# ma_esquema.net
KiCad netlist of a schematic drawn in EAGLE
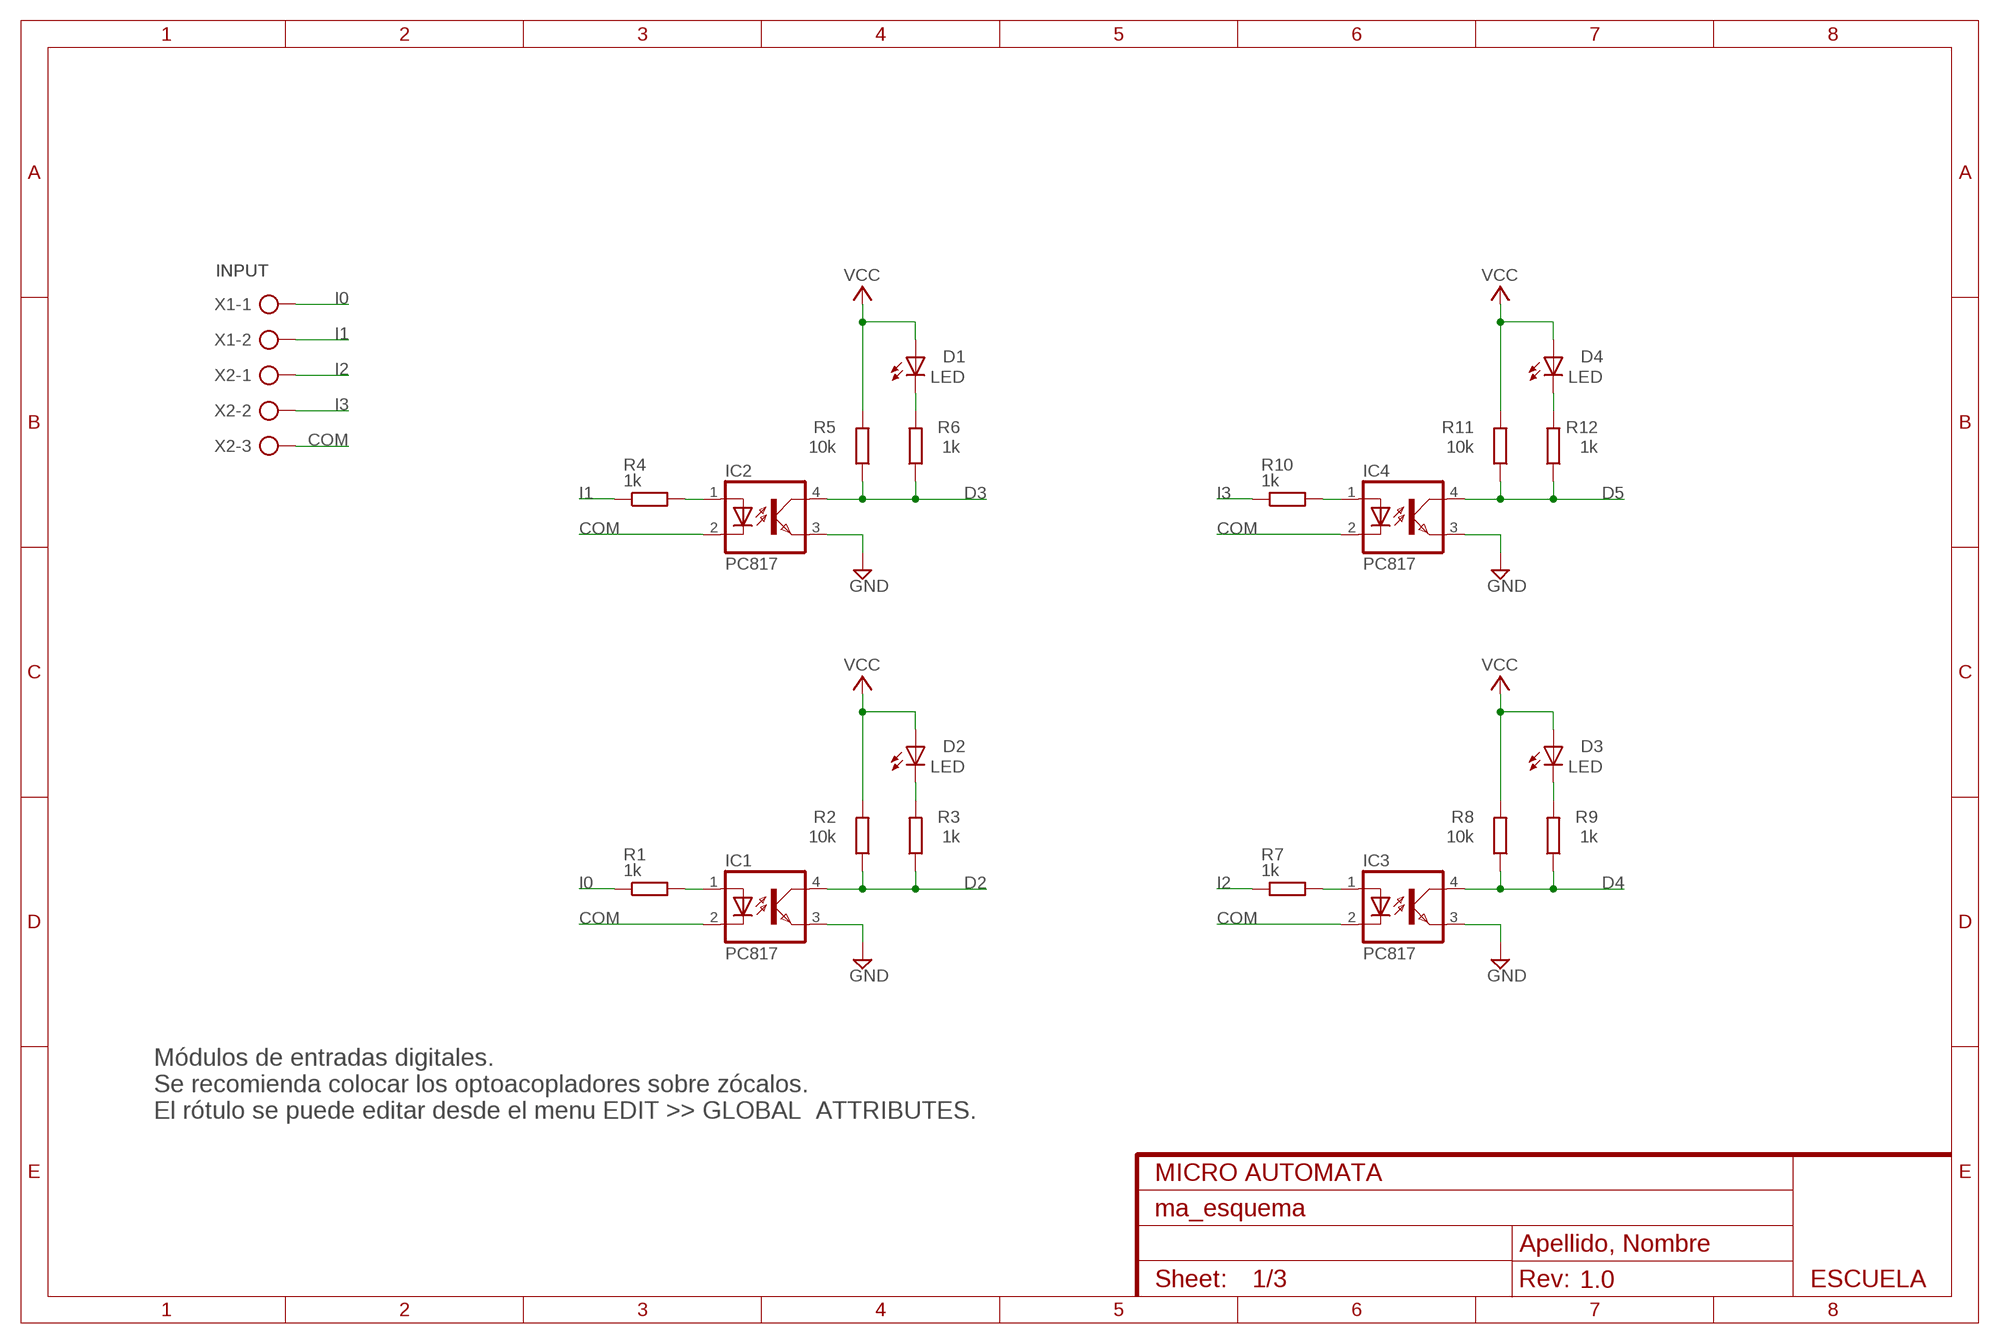
[diagram p0: schematic, sheet 1]
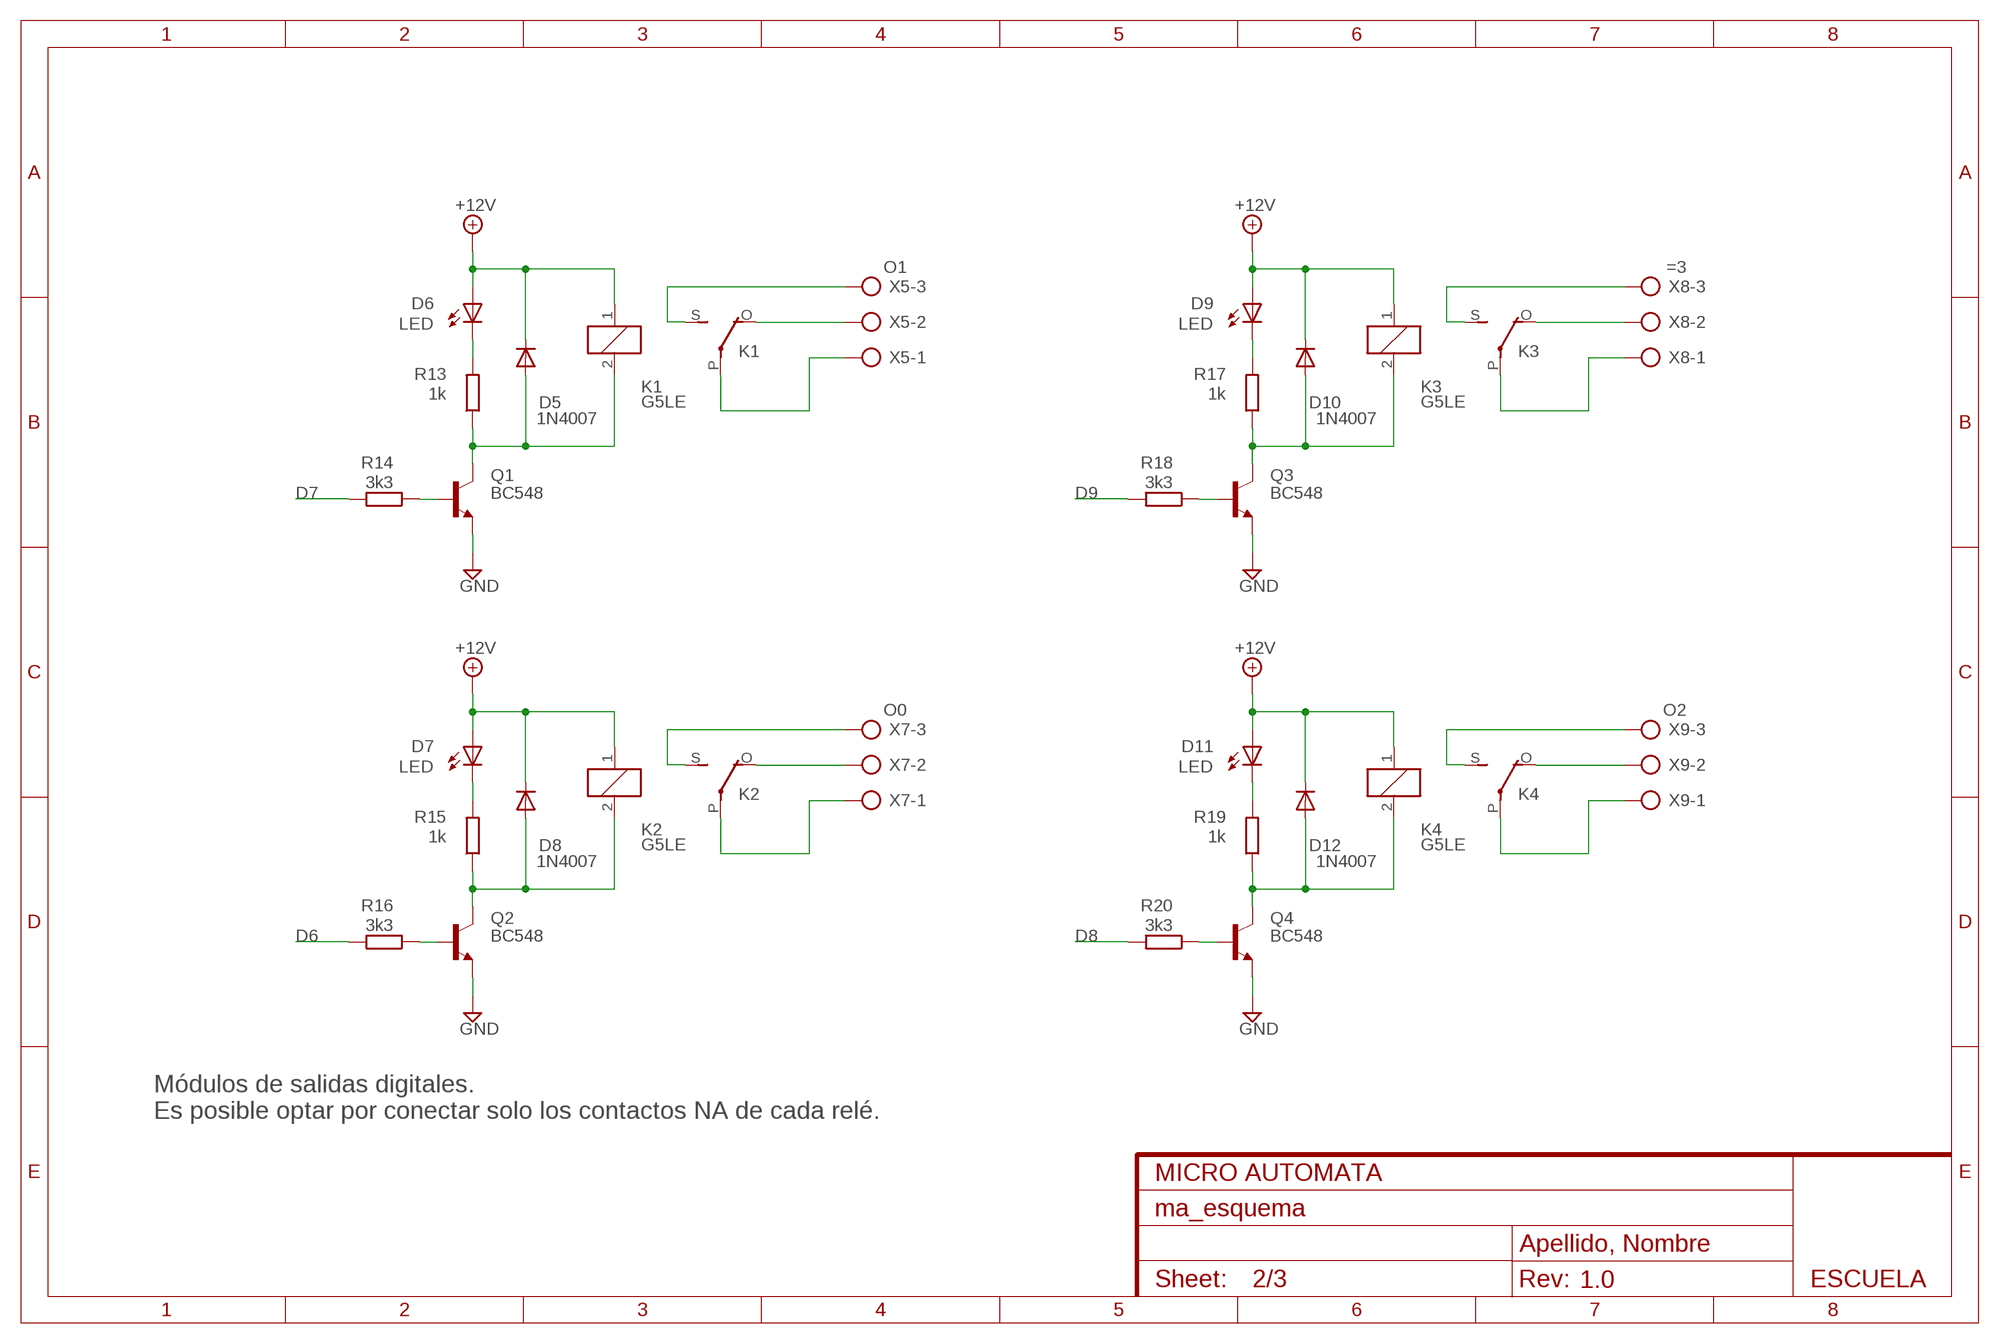
[diagram p1: schematic, sheet 2]
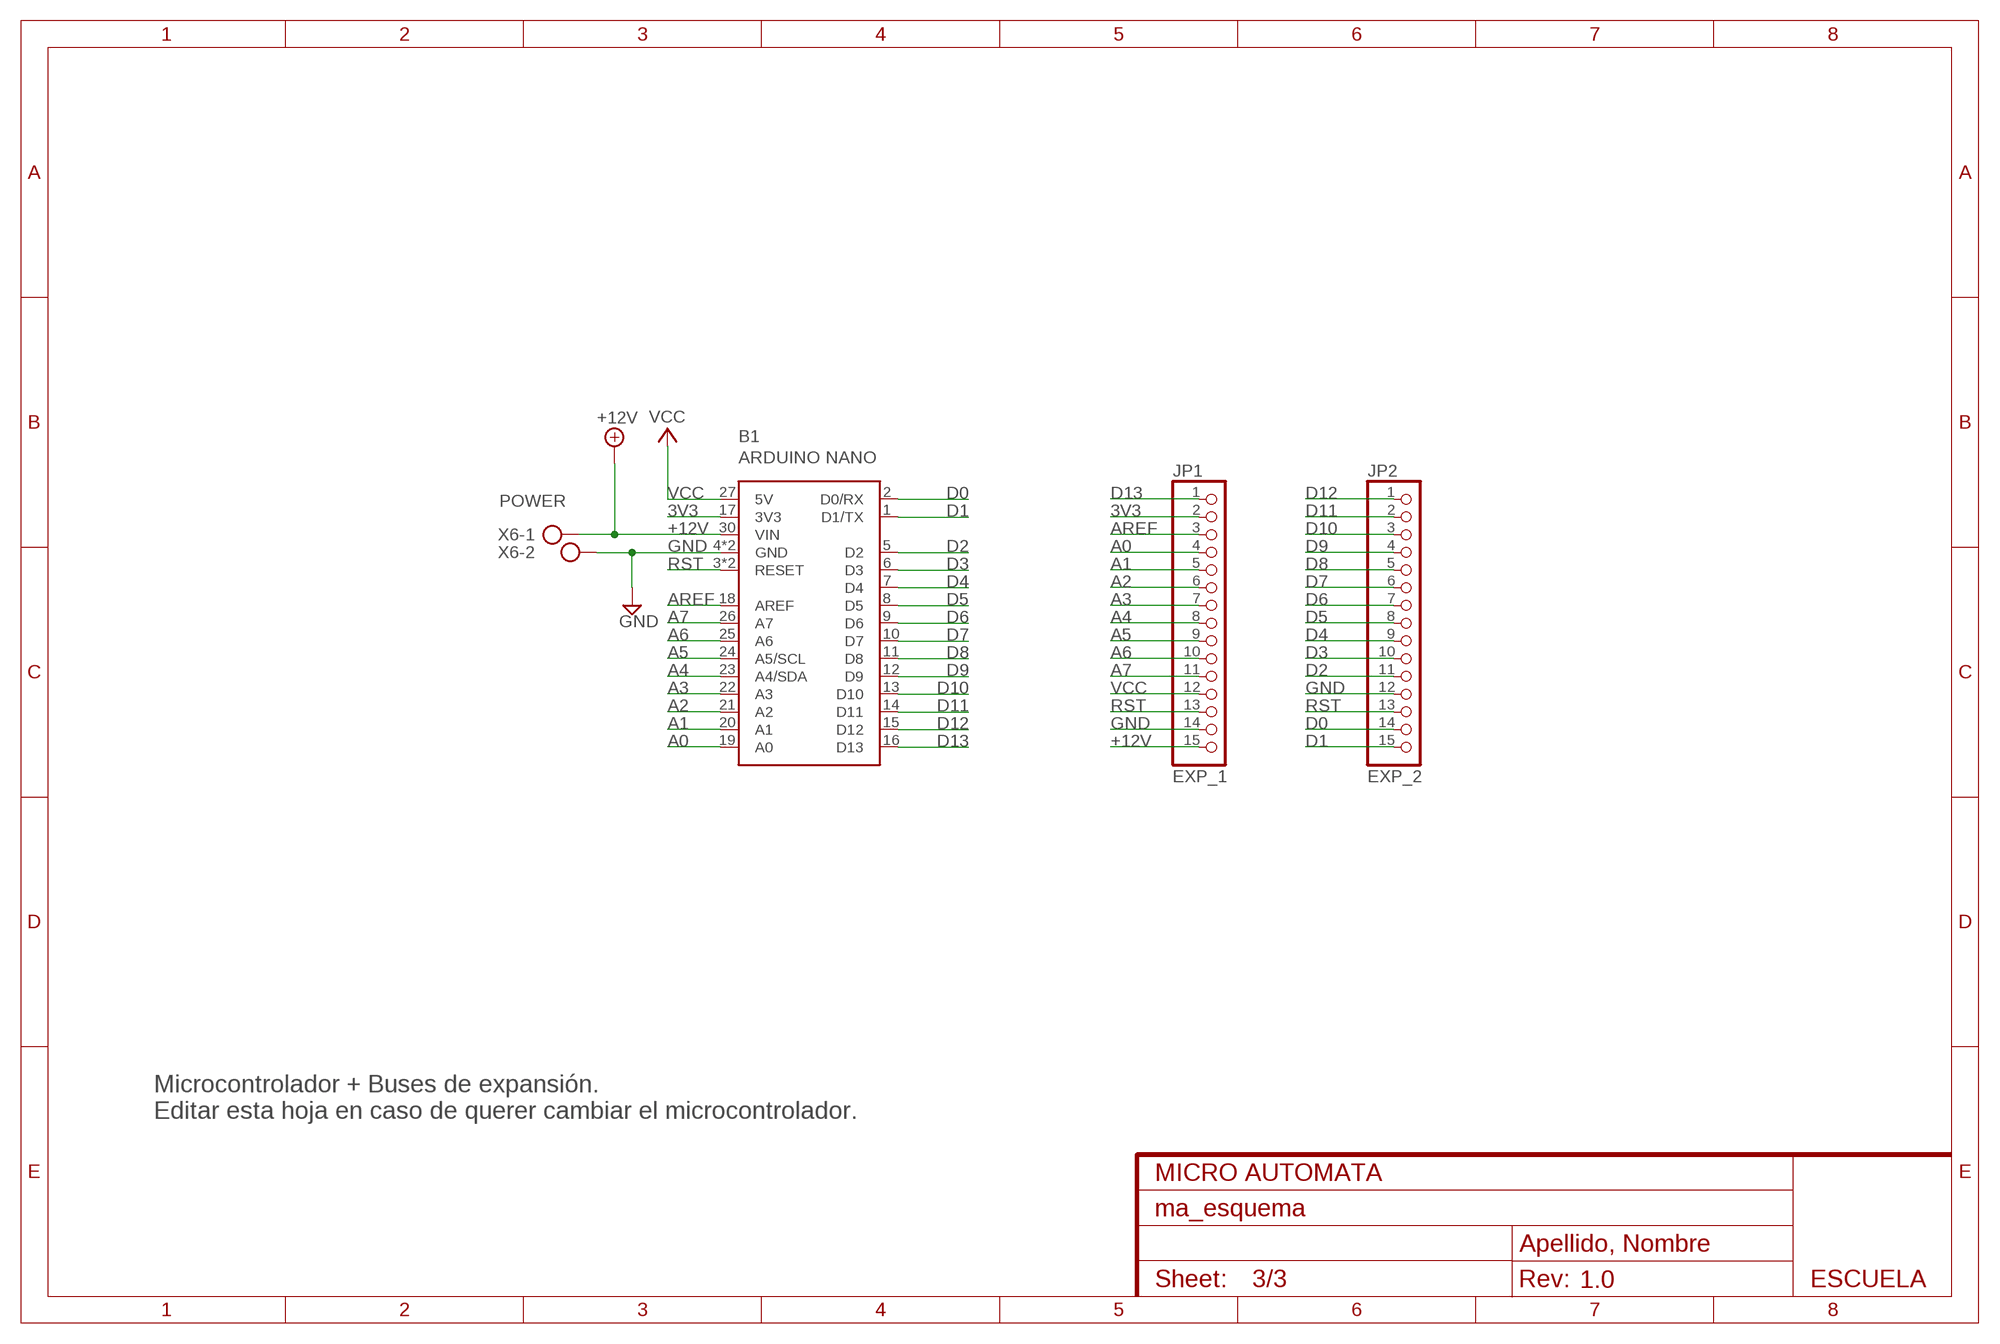
[diagram p2: schematic, sheet 3]

(export (version "E")
  (design (tool "Eeschema 10.0.6"))
  (components
    (comp (ref "D1")
      (value "LED")
      (footprint "eagle-import:LED_3MM")
      (libsource (lib "eagle-import") (part "LED3MM"))
    )
    (comp (ref "D2")
      (value "LED")
      (footprint "eagle-import:LED_3MM")
      (libsource (lib "eagle-import") (part "LED3MM"))
    )
    (comp (ref "D3")
      (value "LED")
      (footprint "eagle-import:LED_3MM")
      (libsource (lib "eagle-import") (part "LED3MM"))
    )
    (comp (ref "D4")
      (value "LED")
      (footprint "eagle-import:LED_3MM")
      (libsource (lib "eagle-import") (part "LED3MM"))
    )
    (comp (ref "IC1")
      (value "PC817")
      (footprint "eagle-import:DIL04")
      (fields (field (name "MPN") "PC817X4J000F"))
      (libsource (lib "eagle-import") (part "PC817"))
    )
    (comp (ref "IC2")
      (value "PC817")
      (footprint "eagle-import:DIL04")
      (fields (field (name "MPN") "PC817X4J000F"))
      (libsource (lib "eagle-import") (part "PC817"))
    )
    (comp (ref "IC3")
      (value "PC817")
      (footprint "eagle-import:DIL04")
      (fields (field (name "MPN") "PC817X4J000F"))
      (libsource (lib "eagle-import") (part "PC817"))
    )
    (comp (ref "IC4")
      (value "PC817")
      (footprint "eagle-import:DIL04")
      (fields (field (name "MPN") "PC817X4J000F"))
      (libsource (lib "eagle-import") (part "PC817"))
    )
    (comp (ref "R1")
      (value "1k")
      (footprint "eagle-import:0204_7")
      (libsource (lib "eagle-import") (part "RESISTOR-EU0204/7"))
    )
    (comp (ref "R2")
      (value "10k")
      (footprint "eagle-import:0204_7")
      (libsource (lib "eagle-import") (part "RESISTOR-EU0204/7"))
    )
    (comp (ref "R3")
      (value "1k")
      (footprint "eagle-import:0204_7")
      (libsource (lib "eagle-import") (part "RESISTOR-EU0204/7"))
    )
    (comp (ref "R4")
      (value "1k")
      (footprint "eagle-import:0204_7")
      (libsource (lib "eagle-import") (part "RESISTOR-EU0204/7"))
    )
    (comp (ref "R5")
      (value "10k")
      (footprint "eagle-import:0204_7")
      (libsource (lib "eagle-import") (part "RESISTOR-EU0204/7"))
    )
    (comp (ref "R6")
      (value "1k")
      (footprint "eagle-import:0204_7")
      (libsource (lib "eagle-import") (part "RESISTOR-EU0204/7"))
    )
    (comp (ref "R7")
      (value "1k")
      (footprint "eagle-import:0204_7")
      (libsource (lib "eagle-import") (part "RESISTOR-EU0204/7"))
    )
    (comp (ref "R8")
      (value "10k")
      (footprint "eagle-import:0204_7")
      (libsource (lib "eagle-import") (part "RESISTOR-EU0204/7"))
    )
    (comp (ref "R9")
      (value "1k")
      (footprint "eagle-import:0204_7")
      (libsource (lib "eagle-import") (part "RESISTOR-EU0204/7"))
    )
    (comp (ref "R10")
      (value "1k")
      (footprint "eagle-import:0204_7")
      (libsource (lib "eagle-import") (part "RESISTOR-EU0204/7"))
    )
    (comp (ref "R11")
      (value "10k")
      (footprint "eagle-import:0204_7")
      (libsource (lib "eagle-import") (part "RESISTOR-EU0204/7"))
    )
    (comp (ref "R12")
      (value "1k")
      (footprint "eagle-import:0204_7")
      (libsource (lib "eagle-import") (part "RESISTOR-EU0204/7"))
    )
    (comp (ref "X1")
      (value "INPUT")
      (footprint "eagle-import:AK500_2")
      (libsource (lib "eagle-import") (part "BORNERA_AK500/2"))
    )
    (comp (ref "X2")
      (value "INPUT")
      (footprint "eagle-import:AK500_3")
      (libsource (lib "eagle-import") (part "BORNERA_AK500/3"))
    )
    (comp (ref "D5")
      (value "1N4007")
      (footprint "eagle-import:DO41-10")
      (libsource (lib "eagle-import") (part "1N4007"))
    )
    (comp (ref "D6")
      (value "LED")
      (footprint "eagle-import:LED_3MM")
      (libsource (lib "eagle-import") (part "LED3MM"))
    )
    (comp (ref "D7")
      (value "LED")
      (footprint "eagle-import:LED_3MM")
      (libsource (lib "eagle-import") (part "LED3MM"))
    )
    (comp (ref "D8")
      (value "1N4007")
      (footprint "eagle-import:DO41-10")
      (libsource (lib "eagle-import") (part "1N4007"))
    )
    (comp (ref "D9")
      (value "LED")
      (footprint "eagle-import:LED_3MM")
      (libsource (lib "eagle-import") (part "LED3MM"))
    )
    (comp (ref "D10")
      (value "1N4007")
      (footprint "eagle-import:DO41-10")
      (libsource (lib "eagle-import") (part "1N4007"))
    )
    (comp (ref "D11")
      (value "LED")
      (footprint "eagle-import:LED_3MM")
      (libsource (lib "eagle-import") (part "LED3MM"))
    )
    (comp (ref "D12")
      (value "1N4007")
      (footprint "eagle-import:DO41-10")
      (libsource (lib "eagle-import") (part "1N4007"))
    )
    (comp (ref "K1")
      (value "G5LE")
      (footprint "eagle-import:G5LE")
      (libsource (lib "eagle-import") (part "RELE_G5LE"))
    )
    (comp (ref "K2")
      (value "G5LE")
      (footprint "eagle-import:G5LE")
      (libsource (lib "eagle-import") (part "RELE_G5LE"))
    )
    (comp (ref "K3")
      (value "G5LE")
      (footprint "eagle-import:G5LE")
      (libsource (lib "eagle-import") (part "RELE_G5LE"))
    )
    (comp (ref "K4")
      (value "G5LE")
      (footprint "eagle-import:G5LE")
      (libsource (lib "eagle-import") (part "RELE_G5LE"))
    )
    (comp (ref "Q1")
      (value "BC548")
      (footprint "eagle-import:TO92-EBC")
      (libsource (lib "eagle-import") (part "BC548"))
    )
    (comp (ref "Q2")
      (value "BC548")
      (footprint "eagle-import:TO92-EBC")
      (libsource (lib "eagle-import") (part "BC548"))
    )
    (comp (ref "Q3")
      (value "BC548")
      (footprint "eagle-import:TO92-EBC")
      (libsource (lib "eagle-import") (part "BC548"))
    )
    (comp (ref "Q4")
      (value "BC548")
      (footprint "eagle-import:TO92-EBC")
      (libsource (lib "eagle-import") (part "BC548"))
    )
    (comp (ref "R13")
      (value "1k")
      (footprint "eagle-import:0204_7")
      (libsource (lib "eagle-import") (part "RESISTOR-EU0204/7"))
    )
    (comp (ref "R14")
      (value "3k3")
      (footprint "eagle-import:0204_7")
      (libsource (lib "eagle-import") (part "RESISTOR-EU0204/7"))
    )
    (comp (ref "R15")
      (value "1k")
      (footprint "eagle-import:0204_7")
      (libsource (lib "eagle-import") (part "RESISTOR-EU0204/7"))
    )
    (comp (ref "R16")
      (value "3k3")
      (footprint "eagle-import:0204_7")
      (libsource (lib "eagle-import") (part "RESISTOR-EU0204/7"))
    )
    (comp (ref "R17")
      (value "1k")
      (footprint "eagle-import:0204_7")
      (libsource (lib "eagle-import") (part "RESISTOR-EU0204/7"))
    )
    (comp (ref "R18")
      (value "3k3")
      (footprint "eagle-import:0204_7")
      (libsource (lib "eagle-import") (part "RESISTOR-EU0204/7"))
    )
    (comp (ref "R19")
      (value "1k")
      (footprint "eagle-import:0204_7")
      (libsource (lib "eagle-import") (part "RESISTOR-EU0204/7"))
    )
    (comp (ref "R20")
      (value "3k3")
      (footprint "eagle-import:0204_7")
      (libsource (lib "eagle-import") (part "RESISTOR-EU0204/7"))
    )
    (comp (ref "X5")
      (value "O1")
      (footprint "eagle-import:AK500_3")
      (libsource (lib "eagle-import") (part "BORNERA_AK500/3"))
    )
    (comp (ref "X7")
      (value "O0")
      (footprint "eagle-import:AK500_3")
      (libsource (lib "eagle-import") (part "BORNERA_AK500/3"))
    )
    (comp (ref "X8")
      (value "=3")
      (footprint "eagle-import:AK500_3")
      (libsource (lib "eagle-import") (part "BORNERA_AK500/3"))
    )
    (comp (ref "X9")
      (value "O2")
      (footprint "eagle-import:AK500_3")
      (libsource (lib "eagle-import") (part "BORNERA_AK500/3"))
    )
    (comp (ref "B1")
      (value "ARDUINO NANO")
      (footprint "eagle-import:NANO")
      (libsource (lib "eagle-import") (part "ARDUINO_NANO"))
    )
    (comp (ref "JP1")
      (value "EXP_1")
      (footprint "eagle-import:1X15")
      (libsource (lib "eagle-import") (part "PINHD-1X15"))
    )
    (comp (ref "JP2")
      (value "EXP_2")
      (footprint "eagle-import:1X15")
      (libsource (lib "eagle-import") (part "PINHD-1X15"))
    )
    (comp (ref "X6")
      (value "POWER")
      (footprint "eagle-import:AK500_2")
      (libsource (lib "eagle-import") (part "BORNERA_AK500/2"))
    )
  )
  (nets
    (net (code "1") (name "+12V") (class "Default")
      (node (ref "B1") (pin "30") (pinfunction "VIN_30") (pintype "bidirectional"))
      (node (ref "D10") (pin "C") (pinfunction "C_C") (pintype "passive"))
      (node (ref "D11") (pin "A") (pinfunction "A_A") (pintype "passive"))
      (node (ref "D12") (pin "C") (pinfunction "C_C") (pintype "passive"))
      (node (ref "D5") (pin "C") (pinfunction "C_C") (pintype "passive"))
      (node (ref "D6") (pin "A") (pinfunction "A_A") (pintype "passive"))
      (node (ref "D7") (pin "A") (pinfunction "A_A") (pintype "passive"))
      (node (ref "D8") (pin "C") (pinfunction "C_C") (pintype "passive"))
      (node (ref "D9") (pin "A") (pinfunction "A_A") (pintype "passive"))
      (node (ref "JP1") (pin "15") (pinfunction "15_15") (pintype "passive"))
      (node (ref "K1") (pin "1") (pinfunction "1_1") (pintype "passive"))
      (node (ref "K2") (pin "1") (pinfunction "1_1") (pintype "passive"))
      (node (ref "K3") (pin "1") (pinfunction "1_1") (pintype "passive"))
      (node (ref "K4") (pin "1") (pinfunction "1_1") (pintype "passive"))
      (node (ref "X6") (pin "1") (pinfunction "KL_1") (pintype "passive"))
    )
    (net (code "2") (name "3V3") (class "Default")
      (node (ref "B1") (pin "17") (pinfunction "3V3_17") (pintype "bidirectional"))
      (node (ref "JP1") (pin "2") (pinfunction "2_2") (pintype "passive"))
    )
    (net (code "3") (name "A0") (class "Default")
      (node (ref "B1") (pin "19") (pinfunction "A0_19") (pintype "bidirectional"))
      (node (ref "JP1") (pin "4") (pinfunction "4_4") (pintype "passive"))
    )
    (net (code "4") (name "A1") (class "Default")
      (node (ref "B1") (pin "20") (pinfunction "A1_20") (pintype "bidirectional"))
      (node (ref "JP1") (pin "5") (pinfunction "5_5") (pintype "passive"))
    )
    (net (code "5") (name "A2") (class "Default")
      (node (ref "B1") (pin "21") (pinfunction "A2_21") (pintype "bidirectional"))
      (node (ref "JP1") (pin "6") (pinfunction "6_6") (pintype "passive"))
    )
    (net (code "6") (name "A3") (class "Default")
      (node (ref "B1") (pin "22") (pinfunction "A3_22") (pintype "bidirectional"))
      (node (ref "JP1") (pin "7") (pinfunction "7_7") (pintype "passive"))
    )
    (net (code "7") (name "A4") (class "Default")
      (node (ref "B1") (pin "23") (pinfunction "A4/SDA_23") (pintype "bidirectional"))
      (node (ref "JP1") (pin "8") (pinfunction "8_8") (pintype "passive"))
    )
    (net (code "8") (name "A5") (class "Default")
      (node (ref "B1") (pin "24") (pinfunction "A5/SCL_24") (pintype "bidirectional"))
      (node (ref "JP1") (pin "9") (pinfunction "9_9") (pintype "passive"))
    )
    (net (code "9") (name "A6") (class "Default")
      (node (ref "B1") (pin "25") (pinfunction "A6_25") (pintype "bidirectional"))
      (node (ref "JP1") (pin "10") (pinfunction "10_10") (pintype "passive"))
    )
    (net (code "10") (name "A7") (class "Default")
      (node (ref "B1") (pin "26") (pinfunction "A7_26") (pintype "bidirectional"))
      (node (ref "JP1") (pin "11") (pinfunction "11_11") (pintype "passive"))
    )
    (net (code "11") (name "AREF") (class "Default")
      (node (ref "B1") (pin "18") (pinfunction "AREF_18") (pintype "bidirectional"))
      (node (ref "JP1") (pin "3") (pinfunction "3_3") (pintype "passive"))
    )
    (net (code "12") (name "COM") (class "Default")
      (node (ref "IC1") (pin "2") (pinfunction "C_2") (pintype "passive"))
      (node (ref "IC2") (pin "2") (pinfunction "C_2") (pintype "passive"))
      (node (ref "IC3") (pin "2") (pinfunction "C_2") (pintype "passive"))
      (node (ref "IC4") (pin "2") (pinfunction "C_2") (pintype "passive"))
      (node (ref "X2") (pin "3") (pinfunction "KL_3") (pintype "passive"))
    )
    (net (code "13") (name "D0") (class "Default")
      (node (ref "B1") (pin "2") (pinfunction "D0/RX_2") (pintype "bidirectional"))
      (node (ref "JP2") (pin "14") (pinfunction "14_14") (pintype "passive"))
    )
    (net (code "14") (name "D1") (class "Default")
      (node (ref "B1") (pin "1") (pinfunction "D1/TX_1") (pintype "bidirectional"))
      (node (ref "JP2") (pin "15") (pinfunction "15_15") (pintype "passive"))
    )
    (net (code "15") (name "D2") (class "Default")
      (node (ref "B1") (pin "5") (pinfunction "D2_5") (pintype "bidirectional"))
      (node (ref "IC1") (pin "4") (pinfunction "COL_4") (pintype "passive"))
      (node (ref "JP2") (pin "11") (pinfunction "11_11") (pintype "passive"))
      (node (ref "R2") (pin "1") (pinfunction "1_1") (pintype "passive"))
      (node (ref "R3") (pin "1") (pinfunction "1_1") (pintype "passive"))
    )
    (net (code "16") (name "D3") (class "Default")
      (node (ref "B1") (pin "6") (pinfunction "D3_6") (pintype "bidirectional"))
      (node (ref "IC2") (pin "4") (pinfunction "COL_4") (pintype "passive"))
      (node (ref "JP2") (pin "10") (pinfunction "10_10") (pintype "passive"))
      (node (ref "R5") (pin "1") (pinfunction "1_1") (pintype "passive"))
      (node (ref "R6") (pin "1") (pinfunction "1_1") (pintype "passive"))
    )
    (net (code "17") (name "D4") (class "Default")
      (node (ref "B1") (pin "7") (pinfunction "D4_7") (pintype "bidirectional"))
      (node (ref "IC3") (pin "4") (pinfunction "COL_4") (pintype "passive"))
      (node (ref "JP2") (pin "9") (pinfunction "9_9") (pintype "passive"))
      (node (ref "R8") (pin "1") (pinfunction "1_1") (pintype "passive"))
      (node (ref "R9") (pin "1") (pinfunction "1_1") (pintype "passive"))
    )
    (net (code "18") (name "D5") (class "Default")
      (node (ref "B1") (pin "8") (pinfunction "D5_8") (pintype "bidirectional"))
      (node (ref "IC4") (pin "4") (pinfunction "COL_4") (pintype "passive"))
      (node (ref "JP2") (pin "8") (pinfunction "8_8") (pintype "passive"))
      (node (ref "R11") (pin "1") (pinfunction "1_1") (pintype "passive"))
      (node (ref "R12") (pin "1") (pinfunction "1_1") (pintype "passive"))
    )
    (net (code "19") (name "D6") (class "Default")
      (node (ref "B1") (pin "9") (pinfunction "D6_9") (pintype "bidirectional"))
      (node (ref "JP2") (pin "7") (pinfunction "7_7") (pintype "passive"))
      (node (ref "R16") (pin "2") (pinfunction "2_2") (pintype "passive"))
    )
    (net (code "20") (name "D7") (class "Default")
      (node (ref "B1") (pin "10") (pinfunction "D7_10") (pintype "bidirectional"))
      (node (ref "JP2") (pin "6") (pinfunction "6_6") (pintype "passive"))
      (node (ref "R14") (pin "2") (pinfunction "2_2") (pintype "passive"))
    )
    (net (code "21") (name "D8") (class "Default")
      (node (ref "B1") (pin "11") (pinfunction "D8_11") (pintype "bidirectional"))
      (node (ref "JP2") (pin "5") (pinfunction "5_5") (pintype "passive"))
      (node (ref "R20") (pin "2") (pinfunction "2_2") (pintype "passive"))
    )
    (net (code "22") (name "D9") (class "Default")
      (node (ref "B1") (pin "12") (pinfunction "D9_12") (pintype "bidirectional"))
      (node (ref "JP2") (pin "4") (pinfunction "4_4") (pintype "passive"))
      (node (ref "R18") (pin "2") (pinfunction "2_2") (pintype "passive"))
    )
    (net (code "23") (name "D10") (class "Default")
      (node (ref "B1") (pin "13") (pinfunction "D10_13") (pintype "bidirectional"))
      (node (ref "JP2") (pin "3") (pinfunction "3_3") (pintype "passive"))
    )
    (net (code "24") (name "D11") (class "Default")
      (node (ref "B1") (pin "14") (pinfunction "D11_14") (pintype "bidirectional"))
      (node (ref "JP2") (pin "2") (pinfunction "2_2") (pintype "passive"))
    )
    (net (code "25") (name "D12") (class "Default")
      (node (ref "B1") (pin "15") (pinfunction "D12_15") (pintype "bidirectional"))
      (node (ref "JP2") (pin "1") (pinfunction "1_1") (pintype "passive"))
    )
    (net (code "26") (name "D13") (class "Default")
      (node (ref "B1") (pin "16") (pinfunction "D13_16") (pintype "bidirectional"))
      (node (ref "JP1") (pin "1") (pinfunction "1_1") (pintype "passive"))
    )
    (net (code "27") (name "GND") (class "Default")
      (node (ref "B1") (pin "29") (pinfunction "GND_29") (pintype "bidirectional"))
      (node (ref "B1") (pin "4") (pinfunction "GND_4") (pintype "bidirectional"))
      (node (ref "IC1") (pin "3") (pinfunction "EMIT_3") (pintype "passive"))
      (node (ref "IC2") (pin "3") (pinfunction "EMIT_3") (pintype "passive"))
      (node (ref "IC3") (pin "3") (pinfunction "EMIT_3") (pintype "passive"))
      (node (ref "IC4") (pin "3") (pinfunction "EMIT_3") (pintype "passive"))
      (node (ref "JP1") (pin "14") (pinfunction "14_14") (pintype "passive"))
      (node (ref "JP2") (pin "12") (pinfunction "12_12") (pintype "passive"))
      (node (ref "Q1") (pin "E") (pinfunction "E_E") (pintype "passive"))
      (node (ref "Q2") (pin "E") (pinfunction "E_E") (pintype "passive"))
      (node (ref "Q3") (pin "E") (pinfunction "E_E") (pintype "passive"))
      (node (ref "Q4") (pin "E") (pinfunction "E_E") (pintype "passive"))
      (node (ref "X6") (pin "2") (pinfunction "KL_2") (pintype "passive"))
    )
    (net (code "28") (name "I0") (class "Default")
      (node (ref "R1") (pin "1") (pinfunction "1_1") (pintype "passive"))
      (node (ref "X1") (pin "1") (pinfunction "KL_1") (pintype "passive"))
    )
    (net (code "29") (name "I1") (class "Default")
      (node (ref "R4") (pin "1") (pinfunction "1_1") (pintype "passive"))
      (node (ref "X1") (pin "2") (pinfunction "KL_2") (pintype "passive"))
    )
    (net (code "30") (name "I2") (class "Default")
      (node (ref "R7") (pin "1") (pinfunction "1_1") (pintype "passive"))
      (node (ref "X2") (pin "1") (pinfunction "KL_1") (pintype "passive"))
    )
    (net (code "31") (name "I3") (class "Default")
      (node (ref "R10") (pin "1") (pinfunction "1_1") (pintype "passive"))
      (node (ref "X2") (pin "2") (pinfunction "KL_2") (pintype "passive"))
    )
    (net (code "32") (name "Net-(D1-C)") (class "Default")
      (node (ref "D1") (pin "K") (pinfunction "C_K") (pintype "passive"))
      (node (ref "R6") (pin "2") (pinfunction "2_2") (pintype "passive"))
    )
    (net (code "33") (name "Net-(D2-C)") (class "Default")
      (node (ref "D2") (pin "K") (pinfunction "C_K") (pintype "passive"))
      (node (ref "R3") (pin "2") (pinfunction "2_2") (pintype "passive"))
    )
    (net (code "34") (name "Net-(D3-C)") (class "Default")
      (node (ref "D3") (pin "K") (pinfunction "C_K") (pintype "passive"))
      (node (ref "R9") (pin "2") (pinfunction "2_2") (pintype "passive"))
    )
    (net (code "35") (name "Net-(D4-C)") (class "Default")
      (node (ref "D4") (pin "K") (pinfunction "C_K") (pintype "passive"))
      (node (ref "R12") (pin "2") (pinfunction "2_2") (pintype "passive"))
    )
    (net (code "36") (name "Net-(D5-PadA)") (class "Default")
      (node (ref "D5") (pin "A") (pinfunction "A_A") (pintype "passive"))
      (node (ref "K1") (pin "2") (pinfunction "2_2") (pintype "passive"))
      (node (ref "Q1") (pin "C") (pinfunction "C_C") (pintype "passive"))
      (node (ref "R13") (pin "1") (pinfunction "1_1") (pintype "passive"))
    )
    (net (code "37") (name "Net-(D6-C)") (class "Default")
      (node (ref "D6") (pin "K") (pinfunction "C_K") (pintype "passive"))
      (node (ref "R13") (pin "2") (pinfunction "2_2") (pintype "passive"))
    )
    (net (code "38") (name "Net-(D7-C)") (class "Default")
      (node (ref "D7") (pin "K") (pinfunction "C_K") (pintype "passive"))
      (node (ref "R15") (pin "2") (pinfunction "2_2") (pintype "passive"))
    )
    (net (code "39") (name "Net-(D8-PadA)") (class "Default")
      (node (ref "D8") (pin "A") (pinfunction "A_A") (pintype "passive"))
      (node (ref "K2") (pin "2") (pinfunction "2_2") (pintype "passive"))
      (node (ref "Q2") (pin "C") (pinfunction "C_C") (pintype "passive"))
      (node (ref "R15") (pin "1") (pinfunction "1_1") (pintype "passive"))
    )
    (net (code "40") (name "Net-(D9-C)") (class "Default")
      (node (ref "D9") (pin "K") (pinfunction "C_K") (pintype "passive"))
      (node (ref "R17") (pin "2") (pinfunction "2_2") (pintype "passive"))
    )
    (net (code "41") (name "Net-(D10-PadA)") (class "Default")
      (node (ref "D10") (pin "A") (pinfunction "A_A") (pintype "passive"))
      (node (ref "K3") (pin "2") (pinfunction "2_2") (pintype "passive"))
      (node (ref "Q3") (pin "C") (pinfunction "C_C") (pintype "passive"))
      (node (ref "R17") (pin "1") (pinfunction "1_1") (pintype "passive"))
    )
    (net (code "42") (name "Net-(D11-C)") (class "Default")
      (node (ref "D11") (pin "K") (pinfunction "C_K") (pintype "passive"))
      (node (ref "R19") (pin "2") (pinfunction "2_2") (pintype "passive"))
    )
    (net (code "43") (name "Net-(D12-PadA)") (class "Default")
      (node (ref "D12") (pin "A") (pinfunction "A_A") (pintype "passive"))
      (node (ref "K4") (pin "2") (pinfunction "2_2") (pintype "passive"))
      (node (ref "Q4") (pin "C") (pinfunction "C_C") (pintype "passive"))
      (node (ref "R19") (pin "1") (pinfunction "1_1") (pintype "passive"))
    )
    (net (code "44") (name "Net-(IC1-A)") (class "Default")
      (node (ref "IC1") (pin "1") (pinfunction "A_1") (pintype "passive"))
      (node (ref "R1") (pin "2") (pinfunction "2_2") (pintype "passive"))
    )
    (net (code "45") (name "Net-(IC2-A)") (class "Default")
      (node (ref "IC2") (pin "1") (pinfunction "A_1") (pintype "passive"))
      (node (ref "R4") (pin "2") (pinfunction "2_2") (pintype "passive"))
    )
    (net (code "46") (name "Net-(IC3-A)") (class "Default")
      (node (ref "IC3") (pin "1") (pinfunction "A_1") (pintype "passive"))
      (node (ref "R7") (pin "2") (pinfunction "2_2") (pintype "passive"))
    )
    (net (code "47") (name "Net-(IC4-A)") (class "Default")
      (node (ref "IC4") (pin "1") (pinfunction "A_1") (pintype "passive"))
      (node (ref "R10") (pin "2") (pinfunction "2_2") (pintype "passive"))
    )
    (net (code "48") (name "Net-(K1B-COM)") (class "Default")
      (node (ref "K1") (pin "P") (pinfunction "COM_P") (pintype "passive"))
      (node (ref "X5") (pin "1") (pinfunction "KL_1") (pintype "passive"))
    )
    (net (code "49") (name "Net-(K1B-NA)") (class "Default")
      (node (ref "K1") (pin "S") (pinfunction "NA_S") (pintype "passive"))
      (node (ref "X5") (pin "3") (pinfunction "KL_3") (pintype "passive"))
    )
    (net (code "50") (name "Net-(K1B-NC)") (class "Default")
      (node (ref "K1") (pin "O") (pinfunction "NC_O") (pintype "passive"))
      (node (ref "X5") (pin "2") (pinfunction "KL_2") (pintype "passive"))
    )
    (net (code "51") (name "Net-(K2B-COM)") (class "Default")
      (node (ref "K2") (pin "P") (pinfunction "COM_P") (pintype "passive"))
      (node (ref "X7") (pin "1") (pinfunction "KL_1") (pintype "passive"))
    )
    (net (code "52") (name "Net-(K2B-NA)") (class "Default")
      (node (ref "K2") (pin "S") (pinfunction "NA_S") (pintype "passive"))
      (node (ref "X7") (pin "3") (pinfunction "KL_3") (pintype "passive"))
    )
    (net (code "53") (name "Net-(K2B-NC)") (class "Default")
      (node (ref "K2") (pin "O") (pinfunction "NC_O") (pintype "passive"))
      (node (ref "X7") (pin "2") (pinfunction "KL_2") (pintype "passive"))
    )
    (net (code "54") (name "Net-(K3B-COM)") (class "Default")
      (node (ref "K3") (pin "P") (pinfunction "COM_P") (pintype "passive"))
      (node (ref "X8") (pin "1") (pinfunction "KL_1") (pintype "passive"))
    )
    (net (code "55") (name "Net-(K3B-NA)") (class "Default")
      (node (ref "K3") (pin "S") (pinfunction "NA_S") (pintype "passive"))
      (node (ref "X8") (pin "3") (pinfunction "KL_3") (pintype "passive"))
    )
    (net (code "56") (name "Net-(K3B-NC)") (class "Default")
      (node (ref "K3") (pin "O") (pinfunction "NC_O") (pintype "passive"))
      (node (ref "X8") (pin "2") (pinfunction "KL_2") (pintype "passive"))
    )
    (net (code "57") (name "Net-(K4B-COM)") (class "Default")
      (node (ref "K4") (pin "P") (pinfunction "COM_P") (pintype "passive"))
      (node (ref "X9") (pin "1") (pinfunction "KL_1") (pintype "passive"))
    )
    (net (code "58") (name "Net-(K4B-NA)") (class "Default")
      (node (ref "K4") (pin "S") (pinfunction "NA_S") (pintype "passive"))
      (node (ref "X9") (pin "3") (pinfunction "KL_3") (pintype "passive"))
    )
    (net (code "59") (name "Net-(K4B-NC)") (class "Default")
      (node (ref "K4") (pin "O") (pinfunction "NC_O") (pintype "passive"))
      (node (ref "X9") (pin "2") (pinfunction "KL_2") (pintype "passive"))
    )
    (net (code "60") (name "Net-(Q1-PadB)") (class "Default")
      (node (ref "Q1") (pin "B") (pinfunction "B_B") (pintype "passive"))
      (node (ref "R14") (pin "1") (pinfunction "1_1") (pintype "passive"))
    )
    (net (code "61") (name "Net-(Q2-PadB)") (class "Default")
      (node (ref "Q2") (pin "B") (pinfunction "B_B") (pintype "passive"))
      (node (ref "R16") (pin "1") (pinfunction "1_1") (pintype "passive"))
    )
    (net (code "62") (name "Net-(Q3-PadB)") (class "Default")
      (node (ref "Q3") (pin "B") (pinfunction "B_B") (pintype "passive"))
      (node (ref "R18") (pin "1") (pinfunction "1_1") (pintype "passive"))
    )
    (net (code "63") (name "Net-(Q4-PadB)") (class "Default")
      (node (ref "Q4") (pin "B") (pinfunction "B_B") (pintype "passive"))
      (node (ref "R20") (pin "1") (pinfunction "1_1") (pintype "passive"))
    )
    (net (code "64") (name "RST") (class "Default")
      (node (ref "B1") (pin "28") (pinfunction "RESET_28") (pintype "bidirectional"))
      (node (ref "B1") (pin "3") (pinfunction "RESET_3") (pintype "bidirectional"))
      (node (ref "JP1") (pin "13") (pinfunction "13_13") (pintype "passive"))
      (node (ref "JP2") (pin "13") (pinfunction "13_13") (pintype "passive"))
    )
    (net (code "65") (name "VCC") (class "Default")
      (node (ref "B1") (pin "27") (pinfunction "5V_27") (pintype "bidirectional"))
      (node (ref "D1") (pin "A") (pinfunction "A_A") (pintype "passive"))
      (node (ref "D2") (pin "A") (pinfunction "A_A") (pintype "passive"))
      (node (ref "D3") (pin "A") (pinfunction "A_A") (pintype "passive"))
      (node (ref "D4") (pin "A") (pinfunction "A_A") (pintype "passive"))
      (node (ref "JP1") (pin "12") (pinfunction "12_12") (pintype "passive"))
      (node (ref "R11") (pin "2") (pinfunction "2_2") (pintype "passive"))
      (node (ref "R2") (pin "2") (pinfunction "2_2") (pintype "passive"))
      (node (ref "R5") (pin "2") (pinfunction "2_2") (pintype "passive"))
      (node (ref "R8") (pin "2") (pinfunction "2_2") (pintype "passive"))
    )
  )
)
